# teensyShield1_5_alt.net
KiCad netlist of a schematic drawn in EAGLE
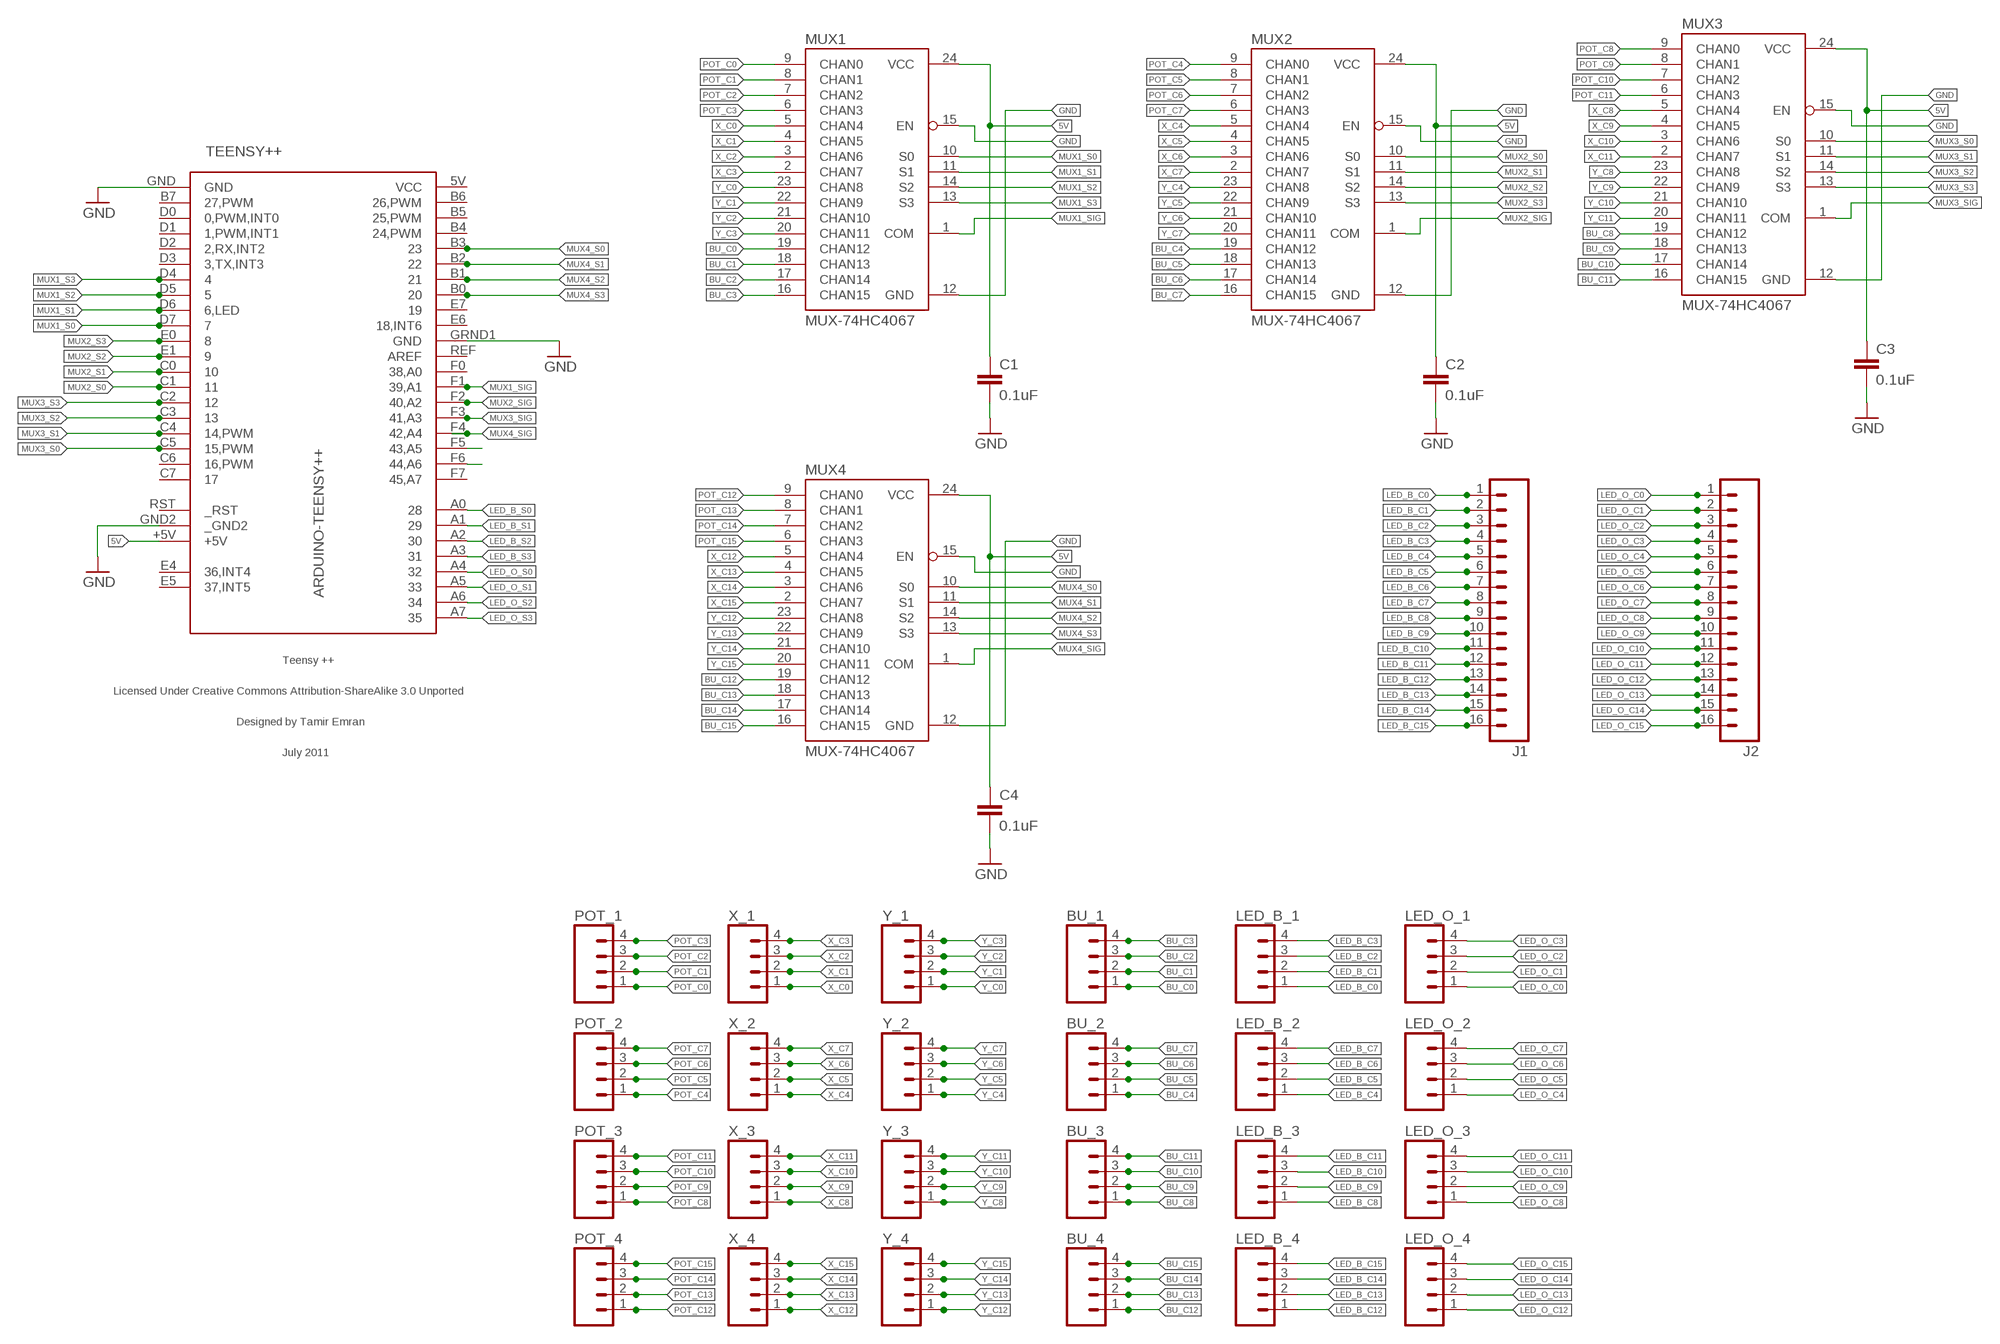
[diagram p0: schematic, sheet 1]

(export (version "E")
  (design (tool "Eeschema 10.0.6"))
  (components
    (comp (ref "BU_1")
      (value "M04NO_SILK_ALL_ROUND")
      (footprint "eagle-import:1X04_NO_SILK_ALL_ROUND")
      (libsource (lib "eagle-import") (part "M04NO_SILK_ALL_ROUND"))
    )
    (comp (ref "BU_2")
      (value "M04NO_SILK_ALL_ROUND")
      (footprint "eagle-import:1X04_NO_SILK_ALL_ROUND")
      (libsource (lib "eagle-import") (part "M04NO_SILK_ALL_ROUND"))
    )
    (comp (ref "BU_3")
      (value "M04NO_SILK_ALL_ROUND")
      (footprint "eagle-import:1X04_NO_SILK_ALL_ROUND")
      (libsource (lib "eagle-import") (part "M04NO_SILK_ALL_ROUND"))
    )
    (comp (ref "BU_4")
      (value "M04NO_SILK_ALL_ROUND")
      (footprint "eagle-import:1X04_NO_SILK_ALL_ROUND")
      (libsource (lib "eagle-import") (part "M04NO_SILK_ALL_ROUND"))
    )
    (comp (ref "C1")
      (value "0.1uF")
      (footprint "eagle-import:0603")
      (libsource (lib "eagle-import") (part "CAP0603"))
    )
    (comp (ref "C2")
      (value "0.1uF")
      (footprint "eagle-import:0603")
      (libsource (lib "eagle-import") (part "CAP0603"))
    )
    (comp (ref "C3")
      (value "0.1uF")
      (footprint "eagle-import:0603")
      (libsource (lib "eagle-import") (part "CAP0603"))
    )
    (comp (ref "C4")
      (value "0.1uF")
      (footprint "eagle-import:0603")
      (libsource (lib "eagle-import") (part "CAP0603"))
    )
    (comp (ref "J1")
      (value "M16MACHIINE-PIN_LOCK")
      (footprint "eagle-import:1X16_MACHINE-PIN-HEADER_LOCK.004")
      (libsource (lib "eagle-import") (part "M16MACHIINE-PIN_LOCK"))
    )
    (comp (ref "J2")
      (value "M16MACHIINE-PIN_LOCK")
      (footprint "eagle-import:1X16_MACHINE-PIN-HEADER_LOCK.004")
      (libsource (lib "eagle-import") (part "M16MACHIINE-PIN_LOCK"))
    )
    (comp (ref "LED_B_1")
      (value "M04NO_SILK_ALL_ROUND")
      (footprint "eagle-import:1X04_NO_SILK_ALL_ROUND")
      (libsource (lib "eagle-import") (part "M04NO_SILK_ALL_ROUND"))
    )
    (comp (ref "LED_B_2")
      (value "M04NO_SILK_ALL_ROUND")
      (footprint "eagle-import:1X04_NO_SILK_ALL_ROUND")
      (libsource (lib "eagle-import") (part "M04NO_SILK_ALL_ROUND"))
    )
    (comp (ref "LED_B_3")
      (value "M04NO_SILK_ALL_ROUND")
      (footprint "eagle-import:1X04_NO_SILK_ALL_ROUND")
      (libsource (lib "eagle-import") (part "M04NO_SILK_ALL_ROUND"))
    )
    (comp (ref "LED_B_4")
      (value "M04NO_SILK_ALL_ROUND")
      (footprint "eagle-import:1X04_NO_SILK_ALL_ROUND")
      (libsource (lib "eagle-import") (part "M04NO_SILK_ALL_ROUND"))
    )
    (comp (ref "LED_O_1")
      (value "M04NO_SILK_ALL_ROUND")
      (footprint "eagle-import:1X04_NO_SILK_ALL_ROUND")
      (libsource (lib "eagle-import") (part "M04NO_SILK_ALL_ROUND"))
    )
    (comp (ref "LED_O_2")
      (value "M04NO_SILK_ALL_ROUND")
      (footprint "eagle-import:1X04_NO_SILK_ALL_ROUND")
      (libsource (lib "eagle-import") (part "M04NO_SILK_ALL_ROUND"))
    )
    (comp (ref "LED_O_3")
      (value "M04NO_SILK_ALL_ROUND")
      (footprint "eagle-import:1X04_NO_SILK_ALL_ROUND")
      (libsource (lib "eagle-import") (part "M04NO_SILK_ALL_ROUND"))
    )
    (comp (ref "LED_O_4")
      (value "M04NO_SILK_ALL_ROUND")
      (footprint "eagle-import:1X04_NO_SILK_ALL_ROUND")
      (libsource (lib "eagle-import") (part "M04NO_SILK_ALL_ROUND"))
    )
    (comp (ref "MUX1")
      (value "MUX-74HC4067")
      (footprint "eagle-import:SSOP24")
      (libsource (lib "eagle-import") (part "MUX-74HC4067SMD"))
    )
    (comp (ref "MUX2")
      (value "MUX-74HC4067")
      (footprint "eagle-import:SSOP24")
      (libsource (lib "eagle-import") (part "MUX-74HC4067SMD"))
    )
    (comp (ref "MUX3")
      (value "MUX-74HC4067")
      (footprint "eagle-import:SSOP24")
      (libsource (lib "eagle-import") (part "MUX-74HC4067SMD"))
    )
    (comp (ref "MUX4")
      (value "MUX-74HC4067")
      (footprint "eagle-import:SSOP24")
      (libsource (lib "eagle-import") (part "MUX-74HC4067SMD"))
    )
    (comp (ref "POT_1")
      (value "M04NO_SILK_ALL_ROUND")
      (footprint "eagle-import:1X04_NO_SILK_ALL_ROUND")
      (libsource (lib "eagle-import") (part "M04NO_SILK_ALL_ROUND"))
    )
    (comp (ref "POT_2")
      (value "M04NO_SILK_ALL_ROUND")
      (footprint "eagle-import:1X04_NO_SILK_ALL_ROUND")
      (libsource (lib "eagle-import") (part "M04NO_SILK_ALL_ROUND"))
    )
    (comp (ref "POT_3")
      (value "M04NO_SILK_ALL_ROUND")
      (footprint "eagle-import:1X04_NO_SILK_ALL_ROUND")
      (libsource (lib "eagle-import") (part "M04NO_SILK_ALL_ROUND"))
    )
    (comp (ref "POT_4")
      (value "M04NO_SILK_ALL_ROUND")
      (footprint "eagle-import:1X04_NO_SILK_ALL_ROUND")
      (libsource (lib "eagle-import") (part "M04NO_SILK_ALL_ROUND"))
    )
    (comp (ref "TEENSY++")
      (value "ARDUINO-TEENSY++")
      (footprint "eagle-import:TEENSY++")
      (libsource (lib "eagle-import") (part "ARDUINO-TEENSY++"))
    )
    (comp (ref "X_1")
      (value "M04NO_SILK_ALL_ROUND")
      (footprint "eagle-import:1X04_NO_SILK_ALL_ROUND")
      (libsource (lib "eagle-import") (part "M04NO_SILK_ALL_ROUND"))
    )
    (comp (ref "X_2")
      (value "M04NO_SILK_ALL_ROUND")
      (footprint "eagle-import:1X04_NO_SILK_ALL_ROUND")
      (libsource (lib "eagle-import") (part "M04NO_SILK_ALL_ROUND"))
    )
    (comp (ref "X_3")
      (value "M04NO_SILK_ALL_ROUND")
      (footprint "eagle-import:1X04_NO_SILK_ALL_ROUND")
      (libsource (lib "eagle-import") (part "M04NO_SILK_ALL_ROUND"))
    )
    (comp (ref "X_4")
      (value "M04NO_SILK_ALL_ROUND")
      (footprint "eagle-import:1X04_NO_SILK_ALL_ROUND")
      (libsource (lib "eagle-import") (part "M04NO_SILK_ALL_ROUND"))
    )
    (comp (ref "Y_1")
      (value "M04NO_SILK_ALL_ROUND")
      (footprint "eagle-import:1X04_NO_SILK_ALL_ROUND")
      (libsource (lib "eagle-import") (part "M04NO_SILK_ALL_ROUND"))
    )
    (comp (ref "Y_2")
      (value "M04NO_SILK_ALL_ROUND")
      (footprint "eagle-import:1X04_NO_SILK_ALL_ROUND")
      (libsource (lib "eagle-import") (part "M04NO_SILK_ALL_ROUND"))
    )
    (comp (ref "Y_3")
      (value "M04NO_SILK_ALL_ROUND")
      (footprint "eagle-import:1X04_NO_SILK_ALL_ROUND")
      (libsource (lib "eagle-import") (part "M04NO_SILK_ALL_ROUND"))
    )
    (comp (ref "Y_4")
      (value "M04NO_SILK_ALL_ROUND")
      (footprint "eagle-import:1X04_NO_SILK_ALL_ROUND")
      (libsource (lib "eagle-import") (part "M04NO_SILK_ALL_ROUND"))
    )
  )
  (nets
    (net (code "1") (name "/VCC") (class "Default")
      (node (ref "TEENSY++") (pin "5V") (pinfunction "VCC_5V") (pintype "power_in"))
    )
    (net (code "2") (name "5V") (class "Default")
      (node (ref "C1") (pin "1") (pinfunction "1_1") (pintype "passive"))
      (node (ref "C2") (pin "1") (pinfunction "1_1") (pintype "passive"))
      (node (ref "C3") (pin "1") (pinfunction "1_1") (pintype "passive"))
      (node (ref "C4") (pin "1") (pinfunction "1_1") (pintype "passive"))
      (node (ref "MUX1") (pin "24") (pinfunction "VCC_24") (pintype "bidirectional"))
      (node (ref "MUX2") (pin "24") (pinfunction "VCC_24") (pintype "bidirectional"))
      (node (ref "MUX3") (pin "24") (pinfunction "VCC_24") (pintype "bidirectional"))
      (node (ref "MUX4") (pin "24") (pinfunction "VCC_24") (pintype "bidirectional"))
    )
    (net (code "3") (name "BU_C0") (class "Default")
      (node (ref "BU_1") (pin "1") (pinfunction "1_1") (pintype "passive"))
      (node (ref "MUX1") (pin "19") (pinfunction "CHAN12_19") (pintype "bidirectional"))
    )
    (net (code "4") (name "BU_C1") (class "Default")
      (node (ref "BU_1") (pin "2") (pinfunction "2_2") (pintype "passive"))
      (node (ref "MUX1") (pin "18") (pinfunction "CHAN13_18") (pintype "bidirectional"))
    )
    (net (code "5") (name "BU_C2") (class "Default")
      (node (ref "BU_1") (pin "3") (pinfunction "3_3") (pintype "passive"))
      (node (ref "MUX1") (pin "17") (pinfunction "CHAN14_17") (pintype "bidirectional"))
    )
    (net (code "6") (name "BU_C3") (class "Default")
      (node (ref "BU_1") (pin "4") (pinfunction "4_4") (pintype "passive"))
      (node (ref "MUX1") (pin "16") (pinfunction "CHAN15_16") (pintype "bidirectional"))
    )
    (net (code "7") (name "BU_C4") (class "Default")
      (node (ref "BU_2") (pin "1") (pinfunction "1_1") (pintype "passive"))
      (node (ref "MUX2") (pin "19") (pinfunction "CHAN12_19") (pintype "bidirectional"))
    )
    (net (code "8") (name "BU_C5") (class "Default")
      (node (ref "BU_2") (pin "2") (pinfunction "2_2") (pintype "passive"))
      (node (ref "MUX2") (pin "18") (pinfunction "CHAN13_18") (pintype "bidirectional"))
    )
    (net (code "9") (name "BU_C6") (class "Default")
      (node (ref "BU_2") (pin "3") (pinfunction "3_3") (pintype "passive"))
      (node (ref "MUX2") (pin "17") (pinfunction "CHAN14_17") (pintype "bidirectional"))
    )
    (net (code "10") (name "BU_C7") (class "Default")
      (node (ref "BU_2") (pin "4") (pinfunction "4_4") (pintype "passive"))
      (node (ref "MUX2") (pin "16") (pinfunction "CHAN15_16") (pintype "bidirectional"))
    )
    (net (code "11") (name "BU_C8") (class "Default")
      (node (ref "BU_3") (pin "1") (pinfunction "1_1") (pintype "passive"))
      (node (ref "MUX3") (pin "19") (pinfunction "CHAN12_19") (pintype "bidirectional"))
    )
    (net (code "12") (name "BU_C9") (class "Default")
      (node (ref "BU_3") (pin "2") (pinfunction "2_2") (pintype "passive"))
      (node (ref "MUX3") (pin "18") (pinfunction "CHAN13_18") (pintype "bidirectional"))
    )
    (net (code "13") (name "BU_C10") (class "Default")
      (node (ref "BU_3") (pin "3") (pinfunction "3_3") (pintype "passive"))
      (node (ref "MUX3") (pin "17") (pinfunction "CHAN14_17") (pintype "bidirectional"))
    )
    (net (code "14") (name "BU_C11") (class "Default")
      (node (ref "BU_3") (pin "4") (pinfunction "4_4") (pintype "passive"))
      (node (ref "MUX3") (pin "16") (pinfunction "CHAN15_16") (pintype "bidirectional"))
    )
    (net (code "15") (name "BU_C12") (class "Default")
      (node (ref "BU_4") (pin "1") (pinfunction "1_1") (pintype "passive"))
      (node (ref "MUX4") (pin "19") (pinfunction "CHAN12_19") (pintype "bidirectional"))
    )
    (net (code "16") (name "BU_C13") (class "Default")
      (node (ref "BU_4") (pin "2") (pinfunction "2_2") (pintype "passive"))
      (node (ref "MUX4") (pin "18") (pinfunction "CHAN13_18") (pintype "bidirectional"))
    )
    (net (code "17") (name "BU_C14") (class "Default")
      (node (ref "BU_4") (pin "3") (pinfunction "3_3") (pintype "passive"))
      (node (ref "MUX4") (pin "17") (pinfunction "CHAN14_17") (pintype "bidirectional"))
    )
    (net (code "18") (name "BU_C15") (class "Default")
      (node (ref "BU_4") (pin "4") (pinfunction "4_4") (pintype "passive"))
      (node (ref "MUX4") (pin "16") (pinfunction "CHAN15_16") (pintype "bidirectional"))
    )
    (net (code "19") (name "GND") (class "Default")
      (node (ref "C1") (pin "2") (pinfunction "2_2") (pintype "passive"))
      (node (ref "C2") (pin "2") (pinfunction "2_2") (pintype "passive"))
      (node (ref "C3") (pin "2") (pinfunction "2_2") (pintype "passive"))
      (node (ref "C4") (pin "2") (pinfunction "2_2") (pintype "passive"))
      (node (ref "MUX1") (pin "12") (pinfunction "GND_12") (pintype "bidirectional"))
      (node (ref "MUX1") (pin "15") (pinfunction "EN_15") (pintype "input"))
      (node (ref "MUX2") (pin "12") (pinfunction "GND_12") (pintype "bidirectional"))
      (node (ref "MUX2") (pin "15") (pinfunction "EN_15") (pintype "input"))
      (node (ref "MUX3") (pin "12") (pinfunction "GND_12") (pintype "bidirectional"))
      (node (ref "MUX3") (pin "15") (pinfunction "EN_15") (pintype "input"))
      (node (ref "MUX4") (pin "12") (pinfunction "GND_12") (pintype "bidirectional"))
      (node (ref "MUX4") (pin "15") (pinfunction "EN_15") (pintype "input"))
      (node (ref "TEENSY++") (pin "GND") (pinfunction "GND_GND") (pintype "power_in"))
      (node (ref "TEENSY++") (pin "GND2") (pinfunction "_GND2_GND2") (pintype "power_in"))
      (node (ref "TEENSY++") (pin "GRND1") (pinfunction "GND_GRND1") (pintype "power_in"))
    )
    (net (code "20") (name "LED_B_C0") (class "Default")
      (node (ref "J1") (pin "1") (pinfunction "1_1") (pintype "passive"))
      (node (ref "LED_B_1") (pin "1") (pinfunction "1_1") (pintype "passive"))
    )
    (net (code "21") (name "LED_B_C1") (class "Default")
      (node (ref "J1") (pin "2") (pinfunction "2_2") (pintype "passive"))
      (node (ref "LED_B_1") (pin "2") (pinfunction "2_2") (pintype "passive"))
    )
    (net (code "22") (name "LED_B_C2") (class "Default")
      (node (ref "J1") (pin "3") (pinfunction "3_3") (pintype "passive"))
      (node (ref "LED_B_1") (pin "3") (pinfunction "3_3") (pintype "passive"))
    )
    (net (code "23") (name "LED_B_C3") (class "Default")
      (node (ref "J1") (pin "4") (pinfunction "4_4") (pintype "passive"))
      (node (ref "LED_B_1") (pin "4") (pinfunction "4_4") (pintype "passive"))
    )
    (net (code "24") (name "LED_B_C4") (class "Default")
      (node (ref "J1") (pin "5") (pinfunction "5_5") (pintype "passive"))
      (node (ref "LED_B_2") (pin "1") (pinfunction "1_1") (pintype "passive"))
    )
    (net (code "25") (name "LED_B_C5") (class "Default")
      (node (ref "J1") (pin "6") (pinfunction "6_6") (pintype "passive"))
      (node (ref "LED_B_2") (pin "2") (pinfunction "2_2") (pintype "passive"))
    )
    (net (code "26") (name "LED_B_C6") (class "Default")
      (node (ref "J1") (pin "7") (pinfunction "7_7") (pintype "passive"))
      (node (ref "LED_B_2") (pin "3") (pinfunction "3_3") (pintype "passive"))
    )
    (net (code "27") (name "LED_B_C7") (class "Default")
      (node (ref "J1") (pin "8") (pinfunction "8_8") (pintype "passive"))
      (node (ref "LED_B_2") (pin "4") (pinfunction "4_4") (pintype "passive"))
    )
    (net (code "28") (name "LED_B_C8") (class "Default")
      (node (ref "J1") (pin "9") (pinfunction "9_9") (pintype "passive"))
      (node (ref "LED_B_3") (pin "1") (pinfunction "1_1") (pintype "passive"))
    )
    (net (code "29") (name "LED_B_C9") (class "Default")
      (node (ref "J1") (pin "10") (pinfunction "10_10") (pintype "passive"))
      (node (ref "LED_B_3") (pin "2") (pinfunction "2_2") (pintype "passive"))
    )
    (net (code "30") (name "LED_B_C10") (class "Default")
      (node (ref "J1") (pin "11") (pinfunction "11_11") (pintype "passive"))
      (node (ref "LED_B_3") (pin "3") (pinfunction "3_3") (pintype "passive"))
    )
    (net (code "31") (name "LED_B_C11") (class "Default")
      (node (ref "J1") (pin "12") (pinfunction "12_12") (pintype "passive"))
      (node (ref "LED_B_3") (pin "4") (pinfunction "4_4") (pintype "passive"))
    )
    (net (code "32") (name "LED_B_C12") (class "Default")
      (node (ref "J1") (pin "13") (pinfunction "13_13") (pintype "passive"))
      (node (ref "LED_B_4") (pin "1") (pinfunction "1_1") (pintype "passive"))
    )
    (net (code "33") (name "LED_B_C13") (class "Default")
      (node (ref "J1") (pin "14") (pinfunction "14_14") (pintype "passive"))
      (node (ref "LED_B_4") (pin "2") (pinfunction "2_2") (pintype "passive"))
    )
    (net (code "34") (name "LED_B_C14") (class "Default")
      (node (ref "J1") (pin "15") (pinfunction "15_15") (pintype "passive"))
      (node (ref "LED_B_4") (pin "3") (pinfunction "3_3") (pintype "passive"))
    )
    (net (code "35") (name "LED_B_C15") (class "Default")
      (node (ref "J1") (pin "16") (pinfunction "16_16") (pintype "passive"))
      (node (ref "LED_B_4") (pin "4") (pinfunction "4_4") (pintype "passive"))
    )
    (net (code "36") (name "LED_B_S0") (class "Default")
      (node (ref "TEENSY++") (pin "A0") (pinfunction "28_A0") (pintype "bidirectional"))
    )
    (net (code "37") (name "LED_B_S1") (class "Default")
      (node (ref "TEENSY++") (pin "A1") (pinfunction "29_A1") (pintype "bidirectional"))
    )
    (net (code "38") (name "LED_B_S2") (class "Default")
      (node (ref "TEENSY++") (pin "A2") (pinfunction "30_A2") (pintype "bidirectional"))
    )
    (net (code "39") (name "LED_B_S3") (class "Default")
      (node (ref "TEENSY++") (pin "A3") (pinfunction "31_A3") (pintype "bidirectional"))
    )
    (net (code "40") (name "LED_O_C0") (class "Default")
      (node (ref "J2") (pin "1") (pinfunction "1_1") (pintype "passive"))
      (node (ref "LED_O_1") (pin "1") (pinfunction "1_1") (pintype "passive"))
    )
    (net (code "41") (name "LED_O_C1") (class "Default")
      (node (ref "J2") (pin "2") (pinfunction "2_2") (pintype "passive"))
      (node (ref "LED_O_1") (pin "2") (pinfunction "2_2") (pintype "passive"))
    )
    (net (code "42") (name "LED_O_C2") (class "Default")
      (node (ref "J2") (pin "3") (pinfunction "3_3") (pintype "passive"))
      (node (ref "LED_O_1") (pin "3") (pinfunction "3_3") (pintype "passive"))
    )
    (net (code "43") (name "LED_O_C3") (class "Default")
      (node (ref "J2") (pin "4") (pinfunction "4_4") (pintype "passive"))
      (node (ref "LED_O_1") (pin "4") (pinfunction "4_4") (pintype "passive"))
    )
    (net (code "44") (name "LED_O_C4") (class "Default")
      (node (ref "J2") (pin "5") (pinfunction "5_5") (pintype "passive"))
      (node (ref "LED_O_2") (pin "1") (pinfunction "1_1") (pintype "passive"))
    )
    (net (code "45") (name "LED_O_C5") (class "Default")
      (node (ref "J2") (pin "6") (pinfunction "6_6") (pintype "passive"))
      (node (ref "LED_O_2") (pin "2") (pinfunction "2_2") (pintype "passive"))
    )
    (net (code "46") (name "LED_O_C6") (class "Default")
      (node (ref "J2") (pin "7") (pinfunction "7_7") (pintype "passive"))
      (node (ref "LED_O_2") (pin "3") (pinfunction "3_3") (pintype "passive"))
    )
    (net (code "47") (name "LED_O_C7") (class "Default")
      (node (ref "J2") (pin "8") (pinfunction "8_8") (pintype "passive"))
      (node (ref "LED_O_2") (pin "4") (pinfunction "4_4") (pintype "passive"))
    )
    (net (code "48") (name "LED_O_C8") (class "Default")
      (node (ref "J2") (pin "9") (pinfunction "9_9") (pintype "passive"))
      (node (ref "LED_O_3") (pin "1") (pinfunction "1_1") (pintype "passive"))
    )
    (net (code "49") (name "LED_O_C9") (class "Default")
      (node (ref "J2") (pin "10") (pinfunction "10_10") (pintype "passive"))
      (node (ref "LED_O_3") (pin "2") (pinfunction "2_2") (pintype "passive"))
    )
    (net (code "50") (name "LED_O_C10") (class "Default")
      (node (ref "J2") (pin "11") (pinfunction "11_11") (pintype "passive"))
      (node (ref "LED_O_3") (pin "3") (pinfunction "3_3") (pintype "passive"))
    )
    (net (code "51") (name "LED_O_C11") (class "Default")
      (node (ref "J2") (pin "12") (pinfunction "12_12") (pintype "passive"))
      (node (ref "LED_O_3") (pin "4") (pinfunction "4_4") (pintype "passive"))
    )
    (net (code "52") (name "LED_O_C12") (class "Default")
      (node (ref "J2") (pin "13") (pinfunction "13_13") (pintype "passive"))
      (node (ref "LED_O_4") (pin "1") (pinfunction "1_1") (pintype "passive"))
    )
    (net (code "53") (name "LED_O_C13") (class "Default")
      (node (ref "J2") (pin "14") (pinfunction "14_14") (pintype "passive"))
      (node (ref "LED_O_4") (pin "2") (pinfunction "2_2") (pintype "passive"))
    )
    (net (code "54") (name "LED_O_C14") (class "Default")
      (node (ref "J2") (pin "15") (pinfunction "15_15") (pintype "passive"))
      (node (ref "LED_O_4") (pin "3") (pinfunction "3_3") (pintype "passive"))
    )
    (net (code "55") (name "LED_O_C15") (class "Default")
      (node (ref "J2") (pin "16") (pinfunction "16_16") (pintype "passive"))
      (node (ref "LED_O_4") (pin "4") (pinfunction "4_4") (pintype "passive"))
    )
    (net (code "56") (name "LED_O_S0") (class "Default")
      (node (ref "TEENSY++") (pin "A4") (pinfunction "32_A4") (pintype "bidirectional"))
    )
    (net (code "57") (name "LED_O_S1") (class "Default")
      (node (ref "TEENSY++") (pin "A5") (pinfunction "33_A5") (pintype "bidirectional"))
    )
    (net (code "58") (name "LED_O_S2") (class "Default")
      (node (ref "TEENSY++") (pin "A6") (pinfunction "34_A6") (pintype "bidirectional"))
    )
    (net (code "59") (name "LED_O_S3") (class "Default")
      (node (ref "TEENSY++") (pin "A7") (pinfunction "35_A7") (pintype "bidirectional"))
    )
    (net (code "60") (name "MUX1_S0") (class "Default")
      (node (ref "MUX1") (pin "10") (pinfunction "S0_10") (pintype "input"))
      (node (ref "TEENSY++") (pin "D7") (pinfunction "7_D7") (pintype "bidirectional"))
    )
    (net (code "61") (name "MUX1_S1") (class "Default")
      (node (ref "MUX1") (pin "11") (pinfunction "S1_11") (pintype "input"))
      (node (ref "TEENSY++") (pin "D6") (pinfunction "6,LED_D6") (pintype "bidirectional"))
    )
    (net (code "62") (name "MUX1_S2") (class "Default")
      (node (ref "MUX1") (pin "14") (pinfunction "S2_14") (pintype "input"))
      (node (ref "TEENSY++") (pin "D5") (pinfunction "5_D5") (pintype "bidirectional"))
    )
    (net (code "63") (name "MUX1_S3") (class "Default")
      (node (ref "MUX1") (pin "13") (pinfunction "S3_13") (pintype "input"))
      (node (ref "TEENSY++") (pin "D4") (pinfunction "4_D4") (pintype "bidirectional"))
    )
    (net (code "64") (name "MUX1_SIG") (class "Default")
      (node (ref "MUX1") (pin "1") (pinfunction "COM_1") (pintype "bidirectional"))
    )
    (net (code "65") (name "MUX2_S0") (class "Default")
      (node (ref "MUX2") (pin "10") (pinfunction "S0_10") (pintype "input"))
      (node (ref "TEENSY++") (pin "C1") (pinfunction "11_C1") (pintype "bidirectional"))
    )
    (net (code "66") (name "MUX2_S1") (class "Default")
      (node (ref "MUX2") (pin "11") (pinfunction "S1_11") (pintype "input"))
      (node (ref "TEENSY++") (pin "C0") (pinfunction "10_C0") (pintype "bidirectional"))
    )
    (net (code "67") (name "MUX2_S2") (class "Default")
      (node (ref "MUX2") (pin "14") (pinfunction "S2_14") (pintype "input"))
      (node (ref "TEENSY++") (pin "E1") (pinfunction "9_E1") (pintype "bidirectional"))
    )
    (net (code "68") (name "MUX2_S3") (class "Default")
      (node (ref "MUX2") (pin "13") (pinfunction "S3_13") (pintype "input"))
      (node (ref "TEENSY++") (pin "E0") (pinfunction "8_E0") (pintype "bidirectional"))
    )
    (net (code "69") (name "MUX2_SIG") (class "Default")
      (node (ref "MUX2") (pin "1") (pinfunction "COM_1") (pintype "bidirectional"))
    )
    (net (code "70") (name "MUX3_S0") (class "Default")
      (node (ref "MUX3") (pin "10") (pinfunction "S0_10") (pintype "input"))
      (node (ref "TEENSY++") (pin "C5") (pinfunction "15,PWM_C5") (pintype "bidirectional"))
    )
    (net (code "71") (name "MUX3_S1") (class "Default")
      (node (ref "MUX3") (pin "11") (pinfunction "S1_11") (pintype "input"))
      (node (ref "TEENSY++") (pin "C4") (pinfunction "14,PWM_C4") (pintype "bidirectional"))
    )
    (net (code "72") (name "MUX3_S2") (class "Default")
      (node (ref "MUX3") (pin "14") (pinfunction "S2_14") (pintype "input"))
      (node (ref "TEENSY++") (pin "C3") (pinfunction "13_C3") (pintype "bidirectional"))
    )
    (net (code "73") (name "MUX3_S3") (class "Default")
      (node (ref "MUX3") (pin "13") (pinfunction "S3_13") (pintype "input"))
      (node (ref "TEENSY++") (pin "C2") (pinfunction "12_C2") (pintype "bidirectional"))
    )
    (net (code "74") (name "MUX3_SIG") (class "Default")
      (node (ref "MUX3") (pin "1") (pinfunction "COM_1") (pintype "bidirectional"))
      (node (ref "TEENSY++") (pin "F3") (pinfunction "41,A3_F3") (pintype "bidirectional"))
    )
    (net (code "75") (name "MUX4_S0") (class "Default")
      (node (ref "MUX4") (pin "10") (pinfunction "S0_10") (pintype "input"))
      (node (ref "TEENSY++") (pin "B3") (pinfunction "23_B3") (pintype "bidirectional"))
    )
    (net (code "76") (name "MUX4_S1") (class "Default")
      (node (ref "MUX4") (pin "11") (pinfunction "S1_11") (pintype "input"))
      (node (ref "TEENSY++") (pin "B2") (pinfunction "22_B2") (pintype "bidirectional"))
    )
    (net (code "77") (name "MUX4_S2") (class "Default")
      (node (ref "MUX4") (pin "14") (pinfunction "S2_14") (pintype "input"))
      (node (ref "TEENSY++") (pin "B1") (pinfunction "21_B1") (pintype "bidirectional"))
    )
    (net (code "78") (name "MUX4_S3") (class "Default")
      (node (ref "MUX4") (pin "13") (pinfunction "S3_13") (pintype "input"))
      (node (ref "TEENSY++") (pin "B0") (pinfunction "20_B0") (pintype "bidirectional"))
    )
    (net (code "79") (name "MUX4_SIG") (class "Default")
      (node (ref "MUX4") (pin "1") (pinfunction "COM_1") (pintype "bidirectional"))
      (node (ref "TEENSY++") (pin "F4") (pinfunction "42,A4_F4") (pintype "bidirectional"))
    )
    (net (code "80") (name "POT_C0") (class "Default")
      (node (ref "MUX1") (pin "9") (pinfunction "CHAN0_9") (pintype "bidirectional"))
      (node (ref "POT_1") (pin "1") (pinfunction "1_1") (pintype "passive"))
    )
    (net (code "81") (name "POT_C1") (class "Default")
      (node (ref "MUX1") (pin "8") (pinfunction "CHAN1_8") (pintype "bidirectional"))
      (node (ref "POT_1") (pin "2") (pinfunction "2_2") (pintype "passive"))
    )
    (net (code "82") (name "POT_C2") (class "Default")
      (node (ref "MUX1") (pin "7") (pinfunction "CHAN2_7") (pintype "bidirectional"))
      (node (ref "POT_1") (pin "3") (pinfunction "3_3") (pintype "passive"))
    )
    (net (code "83") (name "POT_C3") (class "Default")
      (node (ref "MUX1") (pin "6") (pinfunction "CHAN3_6") (pintype "bidirectional"))
      (node (ref "POT_1") (pin "4") (pinfunction "4_4") (pintype "passive"))
    )
    (net (code "84") (name "POT_C4") (class "Default")
      (node (ref "MUX2") (pin "9") (pinfunction "CHAN0_9") (pintype "bidirectional"))
      (node (ref "POT_2") (pin "1") (pinfunction "1_1") (pintype "passive"))
    )
    (net (code "85") (name "POT_C5") (class "Default")
      (node (ref "MUX2") (pin "8") (pinfunction "CHAN1_8") (pintype "bidirectional"))
      (node (ref "POT_2") (pin "2") (pinfunction "2_2") (pintype "passive"))
    )
    (net (code "86") (name "POT_C6") (class "Default")
      (node (ref "MUX2") (pin "7") (pinfunction "CHAN2_7") (pintype "bidirectional"))
      (node (ref "POT_2") (pin "3") (pinfunction "3_3") (pintype "passive"))
    )
    (net (code "87") (name "POT_C7") (class "Default")
      (node (ref "MUX2") (pin "6") (pinfunction "CHAN3_6") (pintype "bidirectional"))
      (node (ref "POT_2") (pin "4") (pinfunction "4_4") (pintype "passive"))
    )
    (net (code "88") (name "POT_C8") (class "Default")
      (node (ref "MUX3") (pin "9") (pinfunction "CHAN0_9") (pintype "bidirectional"))
      (node (ref "POT_3") (pin "1") (pinfunction "1_1") (pintype "passive"))
    )
    (net (code "89") (name "POT_C9") (class "Default")
      (node (ref "MUX3") (pin "8") (pinfunction "CHAN1_8") (pintype "bidirectional"))
      (node (ref "POT_3") (pin "2") (pinfunction "2_2") (pintype "passive"))
    )
    (net (code "90") (name "POT_C10") (class "Default")
      (node (ref "MUX3") (pin "7") (pinfunction "CHAN2_7") (pintype "bidirectional"))
      (node (ref "POT_3") (pin "3") (pinfunction "3_3") (pintype "passive"))
    )
    (net (code "91") (name "POT_C11") (class "Default")
      (node (ref "MUX3") (pin "6") (pinfunction "CHAN3_6") (pintype "bidirectional"))
      (node (ref "POT_3") (pin "4") (pinfunction "4_4") (pintype "passive"))
    )
    (net (code "92") (name "POT_C12") (class "Default")
      (node (ref "MUX4") (pin "9") (pinfunction "CHAN0_9") (pintype "bidirectional"))
      (node (ref "POT_4") (pin "1") (pinfunction "1_1") (pintype "passive"))
    )
    (net (code "93") (name "POT_C13") (class "Default")
      (node (ref "MUX4") (pin "8") (pinfunction "CHAN1_8") (pintype "bidirectional"))
      (node (ref "POT_4") (pin "2") (pinfunction "2_2") (pintype "passive"))
    )
    (net (code "94") (name "POT_C14") (class "Default")
      (node (ref "MUX4") (pin "7") (pinfunction "CHAN2_7") (pintype "bidirectional"))
      (node (ref "POT_4") (pin "3") (pinfunction "3_3") (pintype "passive"))
    )
    (net (code "95") (name "POT_C15") (class "Default")
      (node (ref "MUX4") (pin "6") (pinfunction "CHAN3_6") (pintype "bidirectional"))
      (node (ref "POT_4") (pin "4") (pinfunction "4_4") (pintype "passive"))
    )
    (net (code "96") (name "X_C0") (class "Default")
      (node (ref "MUX1") (pin "5") (pinfunction "CHAN4_5") (pintype "bidirectional"))
      (node (ref "X_1") (pin "1") (pinfunction "1_1") (pintype "passive"))
    )
    (net (code "97") (name "X_C1") (class "Default")
      (node (ref "MUX1") (pin "4") (pinfunction "CHAN5_4") (pintype "bidirectional"))
      (node (ref "X_1") (pin "2") (pinfunction "2_2") (pintype "passive"))
    )
    (net (code "98") (name "X_C2") (class "Default")
      (node (ref "MUX1") (pin "3") (pinfunction "CHAN6_3") (pintype "bidirectional"))
      (node (ref "X_1") (pin "3") (pinfunction "3_3") (pintype "passive"))
    )
    (net (code "99") (name "X_C3") (class "Default")
      (node (ref "MUX1") (pin "2") (pinfunction "CHAN7_2") (pintype "bidirectional"))
      (node (ref "X_1") (pin "4") (pinfunction "4_4") (pintype "passive"))
    )
    (net (code "100") (name "X_C4") (class "Default")
      (node (ref "MUX2") (pin "5") (pinfunction "CHAN4_5") (pintype "bidirectional"))
      (node (ref "X_2") (pin "1") (pinfunction "1_1") (pintype "passive"))
    )
    (net (code "101") (name "X_C5") (class "Default")
      (node (ref "MUX2") (pin "4") (pinfunction "CHAN5_4") (pintype "bidirectional"))
      (node (ref "X_2") (pin "2") (pinfunction "2_2") (pintype "passive"))
    )
    (net (code "102") (name "X_C6") (class "Default")
      (node (ref "MUX2") (pin "3") (pinfunction "CHAN6_3") (pintype "bidirectional"))
      (node (ref "X_2") (pin "3") (pinfunction "3_3") (pintype "passive"))
    )
    (net (code "103") (name "X_C7") (class "Default")
      (node (ref "MUX2") (pin "2") (pinfunction "CHAN7_2") (pintype "bidirectional"))
      (node (ref "X_2") (pin "4") (pinfunction "4_4") (pintype "passive"))
    )
    (net (code "104") (name "X_C8") (class "Default")
      (node (ref "MUX3") (pin "5") (pinfunction "CHAN4_5") (pintype "bidirectional"))
      (node (ref "X_3") (pin "1") (pinfunction "1_1") (pintype "passive"))
    )
    (net (code "105") (name "X_C9") (class "Default")
      (node (ref "MUX3") (pin "4") (pinfunction "CHAN5_4") (pintype "bidirectional"))
      (node (ref "X_3") (pin "2") (pinfunction "2_2") (pintype "passive"))
    )
    (net (code "106") (name "X_C10") (class "Default")
      (node (ref "MUX3") (pin "3") (pinfunction "CHAN6_3") (pintype "bidirectional"))
      (node (ref "X_3") (pin "3") (pinfunction "3_3") (pintype "passive"))
    )
    (net (code "107") (name "X_C11") (class "Default")
      (node (ref "MUX3") (pin "2") (pinfunction "CHAN7_2") (pintype "bidirectional"))
      (node (ref "X_3") (pin "4") (pinfunction "4_4") (pintype "passive"))
    )
    (net (code "108") (name "X_C12") (class "Default")
      (node (ref "MUX4") (pin "5") (pinfunction "CHAN4_5") (pintype "bidirectional"))
      (node (ref "X_4") (pin "1") (pinfunction "1_1") (pintype "passive"))
    )
    (net (code "109") (name "X_C13") (class "Default")
      (node (ref "MUX4") (pin "4") (pinfunction "CHAN5_4") (pintype "bidirectional"))
      (node (ref "X_4") (pin "2") (pinfunction "2_2") (pintype "passive"))
    )
    (net (code "110") (name "X_C14") (class "Default")
      (node (ref "MUX4") (pin "3") (pinfunction "CHAN6_3") (pintype "bidirectional"))
      (node (ref "X_4") (pin "3") (pinfunction "3_3") (pintype "passive"))
    )
    (net (code "111") (name "X_C15") (class "Default")
      (node (ref "MUX4") (pin "2") (pinfunction "CHAN7_2") (pintype "bidirectional"))
      (node (ref "X_4") (pin "4") (pinfunction "4_4") (pintype "passive"))
    )
    (net (code "112") (name "Y_C0") (class "Default")
      (node (ref "MUX1") (pin "23") (pinfunction "CHAN8_23") (pintype "bidirectional"))
      (node (ref "Y_1") (pin "1") (pinfunction "1_1") (pintype "passive"))
    )
    (net (code "113") (name "Y_C1") (class "Default")
      (node (ref "MUX1") (pin "22") (pinfunction "CHAN9_22") (pintype "bidirectional"))
      (node (ref "Y_1") (pin "2") (pinfunction "2_2") (pintype "passive"))
    )
    (net (code "114") (name "Y_C2") (class "Default")
      (node (ref "MUX1") (pin "21") (pinfunction "CHAN10_21") (pintype "bidirectional"))
      (node (ref "Y_1") (pin "3") (pinfunction "3_3") (pintype "passive"))
    )
    (net (code "115") (name "Y_C3") (class "Default")
      (node (ref "MUX1") (pin "20") (pinfunction "CHAN11_20") (pintype "bidirectional"))
      (node (ref "Y_1") (pin "4") (pinfunction "4_4") (pintype "passive"))
    )
    (net (code "116") (name "Y_C4") (class "Default")
      (node (ref "MUX2") (pin "23") (pinfunction "CHAN8_23") (pintype "bidirectional"))
      (node (ref "Y_2") (pin "1") (pinfunction "1_1") (pintype "passive"))
    )
    (net (code "117") (name "Y_C5") (class "Default")
      (node (ref "MUX2") (pin "22") (pinfunction "CHAN9_22") (pintype "bidirectional"))
      (node (ref "Y_2") (pin "2") (pinfunction "2_2") (pintype "passive"))
    )
    (net (code "118") (name "Y_C6") (class "Default")
      (node (ref "MUX2") (pin "21") (pinfunction "CHAN10_21") (pintype "bidirectional"))
      (node (ref "Y_2") (pin "3") (pinfunction "3_3") (pintype "passive"))
    )
    (net (code "119") (name "Y_C7") (class "Default")
      (node (ref "MUX2") (pin "20") (pinfunction "CHAN11_20") (pintype "bidirectional"))
      (node (ref "Y_2") (pin "4") (pinfunction "4_4") (pintype "passive"))
    )
    (net (code "120") (name "Y_C8") (class "Default")
      (node (ref "MUX3") (pin "23") (pinfunction "CHAN8_23") (pintype "bidirectional"))
      (node (ref "Y_3") (pin "1") (pinfunction "1_1") (pintype "passive"))
    )
    (net (code "121") (name "Y_C9") (class "Default")
      (node (ref "MUX3") (pin "22") (pinfunction "CHAN9_22") (pintype "bidirectional"))
      (node (ref "Y_3") (pin "2") (pinfunction "2_2") (pintype "passive"))
    )
    (net (code "122") (name "Y_C10") (class "Default")
      (node (ref "MUX3") (pin "21") (pinfunction "CHAN10_21") (pintype "bidirectional"))
      (node (ref "Y_3") (pin "3") (pinfunction "3_3") (pintype "passive"))
    )
    (net (code "123") (name "Y_C11") (class "Default")
      (node (ref "MUX3") (pin "20") (pinfunction "CHAN11_20") (pintype "bidirectional"))
      (node (ref "Y_3") (pin "4") (pinfunction "4_4") (pintype "passive"))
    )
    (net (code "124") (name "Y_C12") (class "Default")
      (node (ref "MUX4") (pin "23") (pinfunction "CHAN8_23") (pintype "bidirectional"))
      (node (ref "Y_4") (pin "1") (pinfunction "1_1") (pintype "passive"))
    )
    (net (code "125") (name "Y_C13") (class "Default")
      (node (ref "MUX4") (pin "22") (pinfunction "CHAN9_22") (pintype "bidirectional"))
      (node (ref "Y_4") (pin "2") (pinfunction "2_2") (pintype "passive"))
    )
    (net (code "126") (name "Y_C14") (class "Default")
      (node (ref "MUX4") (pin "21") (pinfunction "CHAN10_21") (pintype "bidirectional"))
      (node (ref "Y_4") (pin "3") (pinfunction "3_3") (pintype "passive"))
    )
    (net (code "127") (name "Y_C15") (class "Default")
      (node (ref "MUX4") (pin "20") (pinfunction "CHAN11_20") (pintype "bidirectional"))
      (node (ref "Y_4") (pin "4") (pinfunction "4_4") (pintype "passive"))
    )
    (net (code "128") (name "unconnected-(TEENSY++-0,PWM,INT0-PadD0)") (class "Default")
      (node (ref "TEENSY++") (pin "D0") (pinfunction "0,PWM,INT0_D0") (pintype "bidirectional"))
    )
    (net (code "129") (name "unconnected-(TEENSY++-1,PWM,INT1-PadD1)") (class "Default")
      (node (ref "TEENSY++") (pin "D1") (pinfunction "1,PWM,INT1_D1") (pintype "bidirectional"))
    )
    (net (code "130") (name "unconnected-(TEENSY++-2,RX,INT2-PadD2)") (class "Default")
      (node (ref "TEENSY++") (pin "D2") (pinfunction "2,RX,INT2_D2") (pintype "bidirectional"))
    )
    (net (code "131") (name "unconnected-(TEENSY++-3,TX,INT3-PadD3)") (class "Default")
      (node (ref "TEENSY++") (pin "D3") (pinfunction "3,TX,INT3_D3") (pintype "bidirectional"))
    )
    (net (code "132") (name "unconnected-(TEENSY++-16,PWM-PadC6)") (class "Default")
      (node (ref "TEENSY++") (pin "C6") (pinfunction "16,PWM_C6") (pintype "bidirectional"))
    )
    (net (code "133") (name "unconnected-(TEENSY++-17-PadC7)") (class "Default")
      (node (ref "TEENSY++") (pin "C7") (pinfunction "17_C7") (pintype "bidirectional"))
    )
    (net (code "134") (name "unconnected-(TEENSY++-18,INT6-PadE6)") (class "Default")
      (node (ref "TEENSY++") (pin "E6") (pinfunction "18,INT6_E6") (pintype "bidirectional"))
    )
    (net (code "135") (name "unconnected-(TEENSY++-19-PadE7)") (class "Default")
      (node (ref "TEENSY++") (pin "E7") (pinfunction "19_E7") (pintype "bidirectional"))
    )
    (net (code "136") (name "unconnected-(TEENSY++-24,PWM-PadB4)") (class "Default")
      (node (ref "TEENSY++") (pin "B4") (pinfunction "24,PWM_B4") (pintype "bidirectional"))
    )
    (net (code "137") (name "unconnected-(TEENSY++-25,PWM-PadB5)") (class "Default")
      (node (ref "TEENSY++") (pin "B5") (pinfunction "25,PWM_B5") (pintype "bidirectional"))
    )
    (net (code "138") (name "unconnected-(TEENSY++-26,PWM-PadB6)") (class "Default")
      (node (ref "TEENSY++") (pin "B6") (pinfunction "26,PWM_B6") (pintype "bidirectional"))
    )
    (net (code "139") (name "unconnected-(TEENSY++-27,PWM-PadB7)") (class "Default")
      (node (ref "TEENSY++") (pin "B7") (pinfunction "27,PWM_B7") (pintype "bidirectional"))
    )
    (net (code "140") (name "unconnected-(TEENSY++-36,INT4-PadE4)") (class "Default")
      (node (ref "TEENSY++") (pin "E4") (pinfunction "36,INT4_E4") (pintype "bidirectional"))
    )
    (net (code "141") (name "unconnected-(TEENSY++-37,INT5-PadE5)") (class "Default")
      (node (ref "TEENSY++") (pin "E5") (pinfunction "37,INT5_E5") (pintype "bidirectional"))
    )
    (net (code "142") (name "unconnected-(TEENSY++-38,A0-PadF0)") (class "Default")
      (node (ref "TEENSY++") (pin "F0") (pinfunction "38,A0_F0") (pintype "bidirectional"))
    )
    (net (code "143") (name "unconnected-(TEENSY++-39,A1-PadF1)") (class "Default")
      (node (ref "TEENSY++") (pin "F1") (pinfunction "39,A1_F1") (pintype "bidirectional"))
    )
    (net (code "144") (name "unconnected-(TEENSY++-40,A2-PadF2)") (class "Default")
      (node (ref "TEENSY++") (pin "F2") (pinfunction "40,A2_F2") (pintype "bidirectional"))
    )
    (net (code "145") (name "unconnected-(TEENSY++-43,A5-PadF5)") (class "Default")
      (node (ref "TEENSY++") (pin "F5") (pinfunction "43,A5_F5") (pintype "bidirectional"))
    )
    (net (code "146") (name "unconnected-(TEENSY++-44,A6-PadF6)") (class "Default")
      (node (ref "TEENSY++") (pin "F6") (pinfunction "44,A6_F6") (pintype "bidirectional"))
    )
    (net (code "147") (name "unconnected-(TEENSY++-45,A7-PadF7)") (class "Default")
      (node (ref "TEENSY++") (pin "F7") (pinfunction "45,A7_F7") (pintype "bidirectional"))
    )
    (net (code "148") (name "unconnected-(TEENSY++-AREF-PadREF)") (class "Default")
      (node (ref "TEENSY++") (pin "REF") (pinfunction "AREF_REF") (pintype "input"))
    )
    (net (code "149") (name "unconnected-(TEENSY++-Pad+5V)") (class "Default")
      (node (ref "TEENSY++") (pin "+5V") (pinfunction "+5V_+5V") (pintype "power_in"))
    )
    (net (code "150") (name "unconnected-(TEENSY++-_RST-PadRST)") (class "Default")
      (node (ref "TEENSY++") (pin "RST") (pinfunction "_RST_RST") (pintype "input"))
    )
  )
)
